# Sheet1.net
KiCad netlist of a schematic drawn in Altium Designer
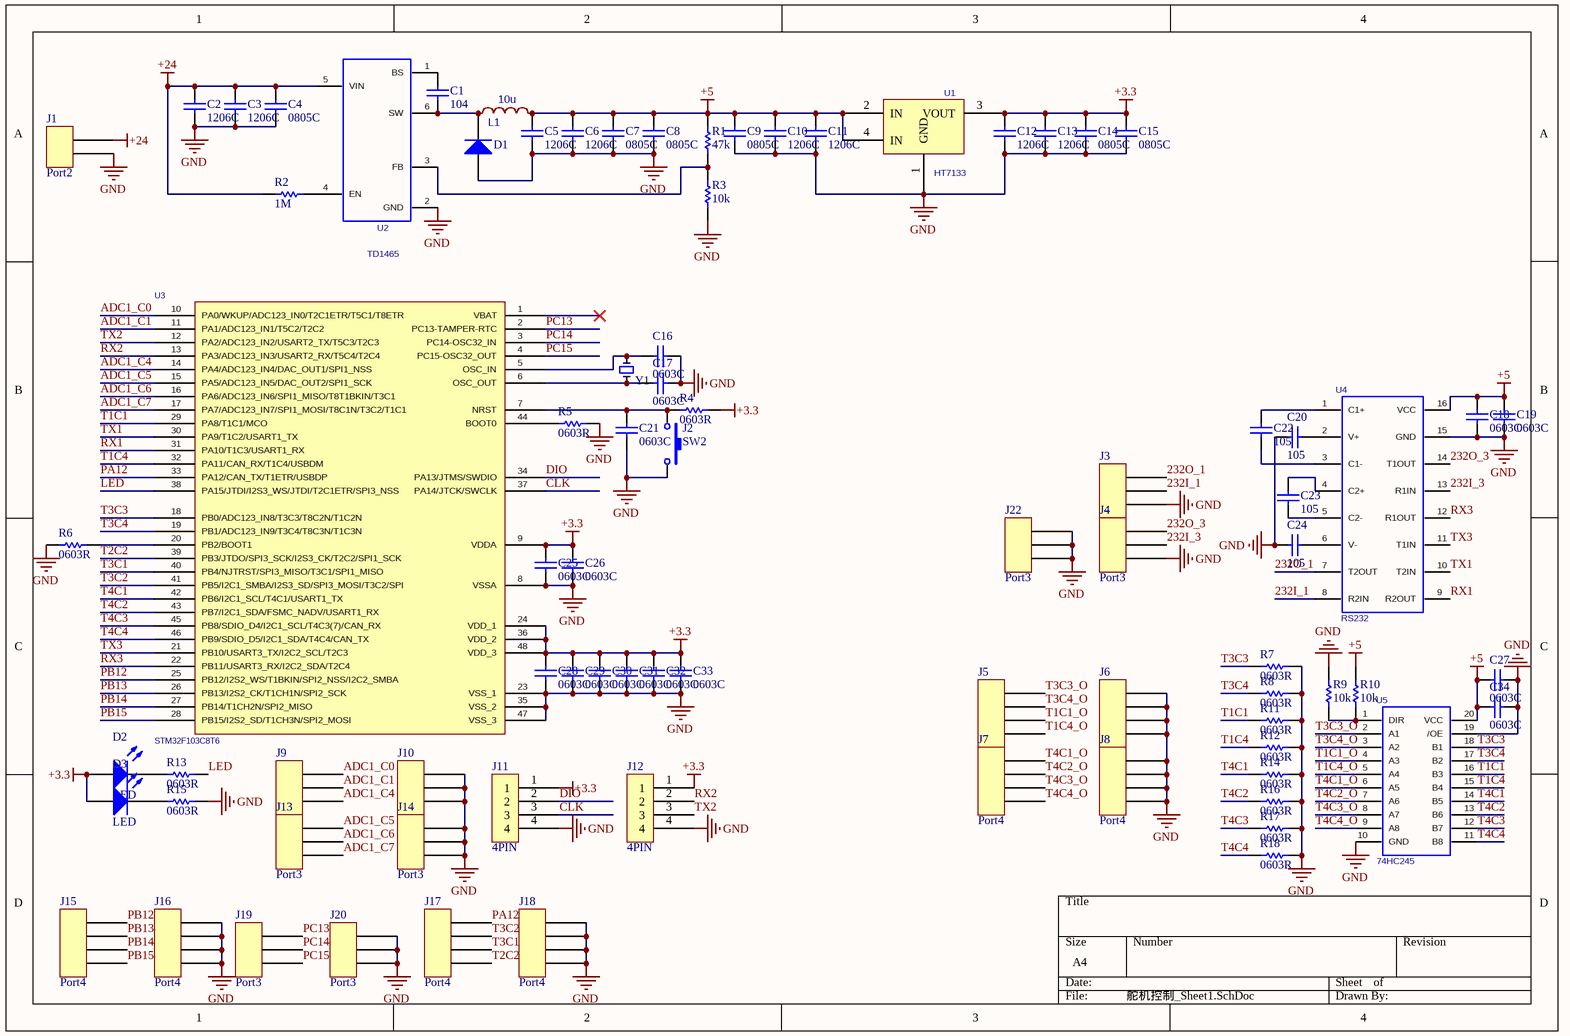
[diagram p0: 舵机控制_Sheet1.SchDoc]

(export (version "E")
  (design (tool "Eeschema 10.0.6"))
  (components
    (comp (ref "C1")
      (value "104")
      (footprint "0603C")
      (fields (field (name "PUBLISHER") "Altium Limited"))
      (libsource (lib "Schlib") (part "0603C"))
    )
    (comp (ref "C2") (value "1206C") (footprint "1206C") (libsource (lib "Schlib") (part "1206C")))
    (comp (ref "C3") (value "1206C") (footprint "1206C") (libsource (lib "Schlib") (part "1206C")))
    (comp (ref "C4") (value "0805C") (footprint "0805C") (libsource (lib "Schlib") (part "0805C")))
    (comp (ref "C5") (value "1206C") (footprint "1206C") (libsource (lib "Schlib") (part "1206C")))
    (comp (ref "C6") (value "1206C") (footprint "1206C") (libsource (lib "Schlib") (part "1206C")))
    (comp (ref "C7") (value "0805C") (footprint "0805C") (libsource (lib "Schlib") (part "0805C")))
    (comp (ref "C8") (value "0805C") (footprint "0805C") (libsource (lib "Schlib") (part "0805C")))
    (comp (ref "C9") (value "0805C") (footprint "0805C") (libsource (lib "Schlib") (part "0805C")))
    (comp (ref "C10") (value "1206C") (footprint "1206C") (libsource (lib "Schlib") (part "1206C")))
    (comp (ref "C11") (value "1206C") (footprint "1206C") (libsource (lib "Schlib") (part "1206C")))
    (comp (ref "C12") (value "1206C") (footprint "1206C") (libsource (lib "Schlib") (part "1206C")))
    (comp (ref "C13") (value "1206C") (footprint "1206C") (libsource (lib "Schlib") (part "1206C")))
    (comp (ref "C14") (value "0805C") (footprint "0805C") (libsource (lib "Schlib") (part "0805C")))
    (comp (ref "C15") (value "0805C") (footprint "0805C") (libsource (lib "Schlib") (part "0805C")))
    (comp (ref "C16")
      (value "0603C")
      (footprint "0603C")
      (fields (field (name "PUBLISHER") "Altium Limited"))
      (libsource (lib "Schlib") (part "0603C"))
    )
    (comp (ref "C17")
      (value "0603C")
      (footprint "0603C")
      (fields (field (name "PUBLISHER") "Altium Limited"))
      (libsource (lib "Schlib") (part "0603C"))
    )
    (comp (ref "C18")
      (value "0603C")
      (footprint "0603C")
      (fields (field (name "PUBLISHER") "Altium Limited"))
      (libsource (lib "Schlib") (part "0603C"))
    )
    (comp (ref "C19")
      (value "0603C")
      (footprint "0603C")
      (fields (field (name "PUBLISHER") "Altium Limited"))
      (libsource (lib "Schlib") (part "0603C"))
    )
    (comp (ref "C20")
      (value "105")
      (footprint "0603C")
      (fields (field (name "PUBLISHER") "Altium Limited"))
      (libsource (lib "Schlib") (part "0603C"))
    )
    (comp (ref "C21")
      (value "0603C")
      (footprint "0603C")
      (fields (field (name "PUBLISHER") "Altium Limited"))
      (libsource (lib "Schlib") (part "0603C"))
    )
    (comp (ref "C22")
      (value "105")
      (footprint "0603C")
      (fields (field (name "PUBLISHER") "Altium Limited"))
      (libsource (lib "Schlib") (part "0603C"))
    )
    (comp (ref "C23")
      (value "105")
      (footprint "0603C")
      (fields (field (name "PUBLISHER") "Altium Limited"))
      (libsource (lib "Schlib") (part "0603C"))
    )
    (comp (ref "C24")
      (value "105")
      (footprint "0603C")
      (fields (field (name "PUBLISHER") "Altium Limited"))
      (libsource (lib "Schlib") (part "0603C"))
    )
    (comp (ref "C25")
      (value "0603C")
      (footprint "0603C")
      (fields (field (name "PUBLISHER") "Altium Limited"))
      (libsource (lib "Schlib") (part "0603C"))
    )
    (comp (ref "C26")
      (value "0603C")
      (footprint "0603C")
      (fields (field (name "PUBLISHER") "Altium Limited"))
      (libsource (lib "Schlib") (part "0603C"))
    )
    (comp (ref "C27")
      (value "0603C")
      (footprint "0603C")
      (fields (field (name "PUBLISHER") "Altium Limited"))
      (libsource (lib "Schlib") (part "0603C"))
    )
    (comp (ref "C28")
      (value "0603C")
      (footprint "0603C")
      (fields (field (name "PUBLISHER") "Altium Limited"))
      (libsource (lib "Schlib") (part "0603C"))
    )
    (comp (ref "C29")
      (value "0603C")
      (footprint "0603C")
      (fields (field (name "PUBLISHER") "Altium Limited"))
      (libsource (lib "Schlib") (part "0603C"))
    )
    (comp (ref "C30")
      (value "0603C")
      (footprint "0603C")
      (fields (field (name "PUBLISHER") "Altium Limited"))
      (libsource (lib "Schlib") (part "0603C"))
    )
    (comp (ref "C31")
      (value "0603C")
      (footprint "0603C")
      (fields (field (name "PUBLISHER") "Altium Limited"))
      (libsource (lib "Schlib") (part "0603C"))
    )
    (comp (ref "C32")
      (value "0603C")
      (footprint "0603C")
      (fields (field (name "PUBLISHER") "Altium Limited"))
      (libsource (lib "Schlib") (part "0603C"))
    )
    (comp (ref "C33")
      (value "0603C")
      (footprint "0603C")
      (fields (field (name "PUBLISHER") "Altium Limited"))
      (libsource (lib "Schlib") (part "0603C"))
    )
    (comp (ref "C34")
      (value "0603C")
      (footprint "0603C")
      (fields (field (name "PUBLISHER") "Altium Limited"))
      (libsource (lib "Schlib") (part "0603C"))
    )
    (comp (ref "D1")
      (value "Diode 1N914")
      (footprint "SOD-123_L2.8-W1.8-LS3.7-RD")
      (fields (field (name "PUBLISHER") "Altium Limited"))
      (libsource (lib "Schlib") (part "Diode 1N914"))
    )
    (comp (ref "D2")
      (value "LED")
      (footprint "0603LED")
      (fields (field (name "PUBLISHER") "Altium Limited"))
      (libsource (lib "Schlib") (part "LED"))
    )
    (comp (ref "D3")
      (value "LED")
      (footprint "0603LED")
      (fields (field (name "PUBLISHER") "Altium Limited"))
      (libsource (lib "Schlib") (part "LED"))
    )
    (comp (ref "J1") (value "Port2") (footprint "Port2") (libsource (lib "Schlib") (part "Port2")))
    (comp (ref "J2")
      (value "SW2")
      (footprint "KEY-SMD_L6.2-W3.6-LS8.0")
      (fields (field (name "PUBLISHER") "Altium Limited"))
      (libsource (lib "Schlib") (part "SW2"))
    )
    (comp (ref "J3") (value "Port3") (footprint "Port3") (libsource (lib "Schlib") (part "Port3")))
    (comp (ref "J4") (value "Port3") (footprint "Port3") (libsource (lib "Schlib") (part "Port3")))
    (comp (ref "J5") (value "Port4") (footprint "Port4") (libsource (lib "Schlib") (part "Port4")))
    (comp (ref "J6") (value "Port4") (footprint "Port4") (libsource (lib "Schlib") (part "Port4")))
    (comp (ref "J7") (value "Port4") (footprint "Port4") (libsource (lib "Schlib") (part "Port4")))
    (comp (ref "J8") (value "Port4") (footprint "Port4") (libsource (lib "Schlib") (part "Port4")))
    (comp (ref "J9") (value "Port3") (footprint "Port3") (libsource (lib "Schlib") (part "Port3")))
    (comp (ref "J10") (value "Port3") (footprint "Port3") (libsource (lib "Schlib") (part "Port3")))
    (comp (ref "J11") (value "4PIN") (footprint "4PIN") (libsource (lib "Schlib") (part "4PIN")))
    (comp (ref "J12") (value "4PIN") (footprint "4PIN") (libsource (lib "Schlib") (part "4PIN")))
    (comp (ref "J13") (value "Port3") (footprint "Port3") (libsource (lib "Schlib") (part "Port3")))
    (comp (ref "J14") (value "Port3") (footprint "Port3") (libsource (lib "Schlib") (part "Port3")))
    (comp (ref "J15") (value "Port4") (footprint "Port4") (libsource (lib "Schlib") (part "Port4")))
    (comp (ref "J16") (value "Port4") (footprint "Port4") (libsource (lib "Schlib") (part "Port4")))
    (comp (ref "J17") (value "Port4") (footprint "Port4") (libsource (lib "Schlib") (part "Port4")))
    (comp (ref "J18") (value "Port4") (footprint "Port4") (libsource (lib "Schlib") (part "Port4")))
    (comp (ref "J19") (value "Port3") (footprint "Port3") (libsource (lib "Schlib") (part "Port3")))
    (comp (ref "J20") (value "Port3") (footprint "Port3") (libsource (lib "Schlib") (part "Port3")))
    (comp (ref "J22") (value "Port3") (footprint "Port3") (libsource (lib "Schlib") (part "Port3")))
    (comp (ref "L1")
      (value "10u")
      (footprint "L-SMD-0630")
      (fields
        (field (name "BOM_MANUFACTURER PART") "FXL0630-100-M")
        (field (name "BOM_SUPPLIER PART") "C167223")
        (field (name "CONTRIBUTOR") "LCSC")
      )
      (libsource (lib "Schlib") (part "L"))
    )
    (comp (ref "R1")
      (value "47k")
      (footprint "0603R")
      (fields (field (name "PUBLISHER") "Altium Limited"))
      (libsource (lib "Schlib") (part "0603R"))
    )
    (comp (ref "R2")
      (value "1M")
      (footprint "0603R")
      (fields (field (name "PUBLISHER") "Altium Limited"))
      (libsource (lib "Schlib") (part "0603R"))
    )
    (comp (ref "R3")
      (value "10k")
      (footprint "0603R")
      (fields (field (name "PUBLISHER") "Altium Limited"))
      (libsource (lib "Schlib") (part "0603R"))
    )
    (comp (ref "R4")
      (value "0603R")
      (footprint "0603R")
      (fields (field (name "PUBLISHER") "Altium Limited"))
      (libsource (lib "Schlib") (part "0603R"))
    )
    (comp (ref "R5")
      (value "0603R")
      (footprint "0603R")
      (fields (field (name "PUBLISHER") "Altium Limited"))
      (libsource (lib "Schlib") (part "0603R"))
    )
    (comp (ref "R6")
      (value "0603R")
      (footprint "0603R")
      (fields (field (name "PUBLISHER") "Altium Limited"))
      (libsource (lib "Schlib") (part "0603R"))
    )
    (comp (ref "R7")
      (value "0603R")
      (footprint "0603R")
      (fields (field (name "PUBLISHER") "Altium Limited"))
      (libsource (lib "Schlib") (part "0603R"))
    )
    (comp (ref "R8")
      (value "0603R")
      (footprint "0603R")
      (fields (field (name "PUBLISHER") "Altium Limited"))
      (libsource (lib "Schlib") (part "0603R"))
    )
    (comp (ref "R9")
      (value "10k")
      (footprint "0603R")
      (fields (field (name "PUBLISHER") "Altium Limited"))
      (libsource (lib "Schlib") (part "0603R"))
    )
    (comp (ref "R10")
      (value "10k")
      (footprint "0603R")
      (fields (field (name "PUBLISHER") "Altium Limited"))
      (libsource (lib "Schlib") (part "0603R"))
    )
    (comp (ref "R11")
      (value "0603R")
      (footprint "0603R")
      (fields (field (name "PUBLISHER") "Altium Limited"))
      (libsource (lib "Schlib") (part "0603R"))
    )
    (comp (ref "R12")
      (value "0603R")
      (footprint "0603R")
      (fields (field (name "PUBLISHER") "Altium Limited"))
      (libsource (lib "Schlib") (part "0603R"))
    )
    (comp (ref "R13")
      (value "0603R")
      (footprint "0603R")
      (fields (field (name "PUBLISHER") "Altium Limited"))
      (libsource (lib "Schlib") (part "0603R"))
    )
    (comp (ref "R14")
      (value "0603R")
      (footprint "0603R")
      (fields (field (name "PUBLISHER") "Altium Limited"))
      (libsource (lib "Schlib") (part "0603R"))
    )
    (comp (ref "R15")
      (value "0603R")
      (footprint "0603R")
      (fields (field (name "PUBLISHER") "Altium Limited"))
      (libsource (lib "Schlib") (part "0603R"))
    )
    (comp (ref "R16")
      (value "0603R")
      (footprint "0603R")
      (fields (field (name "PUBLISHER") "Altium Limited"))
      (libsource (lib "Schlib") (part "0603R"))
    )
    (comp (ref "R17")
      (value "0603R")
      (footprint "0603R")
      (fields (field (name "PUBLISHER") "Altium Limited"))
      (libsource (lib "Schlib") (part "0603R"))
    )
    (comp (ref "R18")
      (value "0603R")
      (footprint "0603R")
      (fields (field (name "PUBLISHER") "Altium Limited"))
      (libsource (lib "Schlib") (part "0603R"))
    )
    (comp (ref "U1")
      (value "HT7133")
      (footprint "SOT-89-3_L4.5-W2.5-P1.50-LS4.2-BR")
      (libsource (lib "Schlib") (part "HT7133"))
    )
    (comp (ref "U2") (value "TD1465") (footprint "SOT-23-6") (libsource (lib "Schlib") (part "TD1465")))
    (comp (ref "U3")
      (value "STM32F103C8T6")
      (footprint "LQFP-48_L7.0-W7.0-P0.50-LS9.0-BL")
      (libsource (lib "Schlib") (part "STM32F103C8T6"))
    )
    (comp (ref "U4")
      (value "RS232")
      (footprint "SOP-16_L9.9-W3.9-P1.27-LS6.1-BL")
      (libsource (lib "Schlib") (part "RS232"))
    )
    (comp (ref "U5")
      (value "74HC245")
      (footprint "TSSOP-20_L6.5-W4.4-P0.65-LS6.4-BL")
      (libsource (lib "Schlib") (part "74HC245"))
    )
    (comp (ref "Y1") (value "XTAL") (footprint "XTAL") (libsource (lib "Schlib") (part "XTAL")))
  )
  (nets
    (net (code "1") (name "+3.3") (class "Default")
      (node (ref "C12") (pin "2") (pinfunction "2_2") (pintype "passive"))
      (node (ref "C13") (pin "2") (pinfunction "2_2") (pintype "passive"))
      (node (ref "C14") (pin "2") (pinfunction "2_2") (pintype "passive"))
      (node (ref "C15") (pin "2") (pinfunction "2_2") (pintype "passive"))
      (node (ref "C25") (pin "2") (pinfunction "2_2") (pintype "passive"))
      (node (ref "C26") (pin "2") (pinfunction "2_2") (pintype "passive"))
      (node (ref "C28") (pin "2") (pinfunction "2_2") (pintype "passive"))
      (node (ref "C29") (pin "2") (pinfunction "2_2") (pintype "passive"))
      (node (ref "C30") (pin "2") (pinfunction "2_2") (pintype "passive"))
      (node (ref "C31") (pin "2") (pinfunction "2_2") (pintype "passive"))
      (node (ref "C32") (pin "2") (pinfunction "2_2") (pintype "passive"))
      (node (ref "C33") (pin "2") (pinfunction "2_2") (pintype "passive"))
      (node (ref "D2") (pin "1") (pinfunction "A_1") (pintype "passive"))
      (node (ref "D3") (pin "1") (pinfunction "A_1") (pintype "passive"))
      (node (ref "J11") (pin "1") (pinfunction "1_1") (pintype "passive"))
      (node (ref "J12") (pin "1") (pinfunction "1_1") (pintype "passive"))
      (node (ref "R4") (pin "1") (pinfunction "1_1") (pintype "passive"))
      (node (ref "U1") (pin "3") (pinfunction "VOUT_3") (pintype "passive"))
      (node (ref "U3") (pin "24") (pinfunction "VDD_1_24") (pintype "passive"))
      (node (ref "U3") (pin "36") (pinfunction "VDD_2_36") (pintype "passive"))
      (node (ref "U3") (pin "48") (pinfunction "VDD_3_48") (pintype "passive"))
      (node (ref "U3") (pin "9") (pinfunction "VDDA_9") (pintype "passive"))
    )
    (net (code "2") (name "+5") (class "Default")
      (node (ref "C10") (pin "2") (pinfunction "2_2") (pintype "passive"))
      (node (ref "C11") (pin "2") (pinfunction "2_2") (pintype "passive"))
      (node (ref "C18") (pin "2") (pinfunction "2_2") (pintype "passive"))
      (node (ref "C19") (pin "2") (pinfunction "2_2") (pintype "passive"))
      (node (ref "C27") (pin "2") (pinfunction "2_2") (pintype "passive"))
      (node (ref "C34") (pin "2") (pinfunction "2_2") (pintype "passive"))
      (node (ref "C5") (pin "2") (pinfunction "2_2") (pintype "passive"))
      (node (ref "C6") (pin "2") (pinfunction "2_2") (pintype "passive"))
      (node (ref "C7") (pin "2") (pinfunction "2_2") (pintype "passive"))
      (node (ref "C8") (pin "2") (pinfunction "2_2") (pintype "passive"))
      (node (ref "C9") (pin "2") (pinfunction "2_2") (pintype "passive"))
      (node (ref "L1") (pin "2") (pinfunction "2_2") (pintype "passive"))
      (node (ref "R1") (pin "2") (pinfunction "2_2") (pintype "passive"))
      (node (ref "R10") (pin "2") (pinfunction "2_2") (pintype "passive"))
      (node (ref "U1") (pin "2") (pinfunction "IN_2") (pintype "passive"))
      (node (ref "U1") (pin "4") (pinfunction "IN_4") (pintype "passive"))
      (node (ref "U4") (pin "16") (pinfunction "VCC_16") (pintype "passive"))
      (node (ref "U5") (pin "20") (pinfunction "VCC_20") (pintype "passive"))
    )
    (net (code "3") (name "+24") (class "Default")
      (node (ref "C2") (pin "2") (pinfunction "2_2") (pintype "passive"))
      (node (ref "C3") (pin "2") (pinfunction "2_2") (pintype "passive"))
      (node (ref "C4") (pin "2") (pinfunction "2_2") (pintype "passive"))
      (node (ref "J1") (pin "2") (pinfunction "2_2") (pintype "passive"))
      (node (ref "R2") (pin "1") (pinfunction "1_1") (pintype "passive"))
      (node (ref "U2") (pin "5") (pinfunction "VIN_5") (pintype "passive"))
    )
    (net (code "4") (name "/232I_1") (class "Default")
      (node (ref "J3") (pin "2") (pinfunction "2_2") (pintype "passive"))
      (node (ref "U4") (pin "8") (pinfunction "R2IN_8") (pintype "passive"))
    )
    (net (code "5") (name "/232I_3") (class "Default")
      (node (ref "J4") (pin "2") (pinfunction "2_2") (pintype "passive"))
      (node (ref "U4") (pin "13") (pinfunction "R1IN_13") (pintype "passive"))
    )
    (net (code "6") (name "/232O_1") (class "Default")
      (node (ref "J3") (pin "1") (pinfunction "1_1") (pintype "passive"))
      (node (ref "U4") (pin "7") (pinfunction "T2OUT_7") (pintype "passive"))
    )
    (net (code "7") (name "/232O_3") (class "Default")
      (node (ref "J4") (pin "1") (pinfunction "1_1") (pintype "passive"))
      (node (ref "U4") (pin "14") (pinfunction "T1OUT_14") (pintype "passive"))
    )
    (net (code "8") (name "/ADC1_C0") (class "Default")
      (node (ref "J9") (pin "1") (pinfunction "1_1") (pintype "passive"))
      (node (ref "U3") (pin "10") (pinfunction "PA0/WKUP/ADC123_IN0/T2C1ETR/T5C1/T8ETR_10") (pintype "passive"))
    )
    (net (code "9") (name "/ADC1_C1") (class "Default")
      (node (ref "J9") (pin "2") (pinfunction "2_2") (pintype "passive"))
      (node (ref "U3") (pin "11") (pinfunction "PA1/ADC123_IN1/T5C2/T2C2_11") (pintype "passive"))
    )
    (net (code "10") (name "/ADC1_C4") (class "Default")
      (node (ref "J9") (pin "3") (pinfunction "3_3") (pintype "passive"))
      (node (ref "U3") (pin "14") (pinfunction "PA4/ADC123_IN4/DAC_OUT1/SPI1_NSS_14") (pintype "passive"))
    )
    (net (code "11") (name "/ADC1_C5") (class "Default")
      (node (ref "J13") (pin "1") (pinfunction "1_1") (pintype "passive"))
      (node (ref "U3") (pin "15") (pinfunction "PA5/ADC123_IN5/DAC_OUT2/SPI1_SCK_15") (pintype "passive"))
    )
    (net (code "12") (name "/ADC1_C6") (class "Default")
      (node (ref "J13") (pin "2") (pinfunction "2_2") (pintype "passive"))
      (node (ref "U3") (pin "16") (pinfunction "PA6/ADC123_IN6/SPI1_MISO/T8T1BKIN/T3C1_16") (pintype "passive"))
    )
    (net (code "13") (name "/ADC1_C7") (class "Default")
      (node (ref "J13") (pin "3") (pinfunction "3_3") (pintype "passive"))
      (node (ref "U3") (pin "17") (pinfunction "PA7/ADC123_IN7/SPI1_MOSI/T8C1N/T3C2/T1C1_17") (pintype "passive"))
    )
    (net (code "14") (name "/CLK") (class "Default")
      (node (ref "J11") (pin "3") (pinfunction "3_3") (pintype "passive"))
      (node (ref "U3") (pin "37") (pinfunction "PA14/JTCK/SWCLK_37") (pintype "passive"))
    )
    (net (code "15") (name "/DIO") (class "Default")
      (node (ref "J11") (pin "2") (pinfunction "2_2") (pintype "passive"))
      (node (ref "U3") (pin "34") (pinfunction "PA13/JTMS/SWDIO_34") (pintype "passive"))
    )
    (net (code "16") (name "/LED") (class "Default")
      (node (ref "R13") (pin "2") (pinfunction "2_2") (pintype "passive"))
      (node (ref "U3") (pin "38") (pinfunction "PA15/JTDI/I2S3_WS/JTDI/T2C1ETR/SPI3_NSS_38") (pintype "passive"))
    )
    (net (code "17") (name "/PA12") (class "Default")
      (node (ref "J17") (pin "1") (pinfunction "1_1") (pintype "passive"))
      (node (ref "U3") (pin "33") (pinfunction "PA12/CAN_TX/T1ETR/USBDP_33") (pintype "passive"))
    )
    (net (code "18") (name "/PB12") (class "Default")
      (node (ref "J15") (pin "1") (pinfunction "1_1") (pintype "passive"))
      (node (ref "U3") (pin "25") (pinfunction "PB12/I2S2_WS/T1BKIN/SPI2_NSS/I2C2_SMBA_25") (pintype "passive"))
    )
    (net (code "19") (name "/PB13") (class "Default")
      (node (ref "J15") (pin "2") (pinfunction "2_2") (pintype "passive"))
      (node (ref "U3") (pin "26") (pinfunction "PB13/I2S2_CK/T1CH1N/SPI2_SCK_26") (pintype "passive"))
    )
    (net (code "20") (name "/PB14") (class "Default")
      (node (ref "J15") (pin "3") (pinfunction "3_3") (pintype "passive"))
      (node (ref "U3") (pin "27") (pinfunction "PB14/T1CH2N/SPI2_MISO_27") (pintype "passive"))
    )
    (net (code "21") (name "/PB15") (class "Default")
      (node (ref "J15") (pin "4") (pinfunction "4_4") (pintype "passive"))
      (node (ref "U3") (pin "28") (pinfunction "PB15/I2S2_SD/T1CH3N/SPI2_MOSI_28") (pintype "passive"))
    )
    (net (code "22") (name "/PC13") (class "Default")
      (node (ref "J19") (pin "1") (pinfunction "1_1") (pintype "passive"))
      (node (ref "U3") (pin "2") (pinfunction "PC13-TAMPER-RTC_2") (pintype "passive"))
    )
    (net (code "23") (name "/PC14") (class "Default")
      (node (ref "J19") (pin "2") (pinfunction "2_2") (pintype "passive"))
      (node (ref "U3") (pin "3") (pinfunction "PC14-OSC32_IN_3") (pintype "passive"))
    )
    (net (code "24") (name "/PC15") (class "Default")
      (node (ref "J19") (pin "3") (pinfunction "3_3") (pintype "passive"))
      (node (ref "U3") (pin "4") (pinfunction "PC15-OSC32_OUT_4") (pintype "passive"))
    )
    (net (code "25") (name "/RX1") (class "Default")
      (node (ref "U3") (pin "31") (pinfunction "PA10/T1C3/USART1_RX_31") (pintype "passive"))
      (node (ref "U4") (pin "9") (pinfunction "R2OUT_9") (pintype "passive"))
    )
    (net (code "26") (name "/RX2") (class "Default")
      (node (ref "J12") (pin "2") (pinfunction "2_2") (pintype "passive"))
      (node (ref "U3") (pin "13") (pinfunction "PA3/ADC123_IN3/USART2_RX/T5C4/T2C4_13") (pintype "passive"))
    )
    (net (code "27") (name "/RX3") (class "Default")
      (node (ref "U3") (pin "22") (pinfunction "PB11/USART3_RX/I2C2_SDA/T2C4_22") (pintype "passive"))
      (node (ref "U4") (pin "12") (pinfunction "R1OUT_12") (pintype "passive"))
    )
    (net (code "28") (name "/T1C1") (class "Default")
      (node (ref "R11") (pin "1") (pinfunction "1_1") (pintype "passive"))
      (node (ref "U3") (pin "29") (pinfunction "PA8/T1C1/MCO_29") (pintype "passive"))
      (node (ref "U5") (pin "16") (pinfunction "B3_16") (pintype "passive"))
    )
    (net (code "29") (name "/T1C1_O") (class "Default")
      (node (ref "J5") (pin "3") (pinfunction "3_3") (pintype "passive"))
      (node (ref "U5") (pin "4") (pinfunction "A3_4") (pintype "passive"))
    )
    (net (code "30") (name "/T1C4") (class "Default")
      (node (ref "R12") (pin "1") (pinfunction "1_1") (pintype "passive"))
      (node (ref "U3") (pin "32") (pinfunction "PA11/CAN_RX/T1C4/USBDM_32") (pintype "passive"))
      (node (ref "U5") (pin "15") (pinfunction "B4_15") (pintype "passive"))
    )
    (net (code "31") (name "/T1C4_O") (class "Default")
      (node (ref "J5") (pin "4") (pinfunction "4_4") (pintype "passive"))
      (node (ref "U5") (pin "5") (pinfunction "A4_5") (pintype "passive"))
    )
    (net (code "32") (name "/T2C2") (class "Default")
      (node (ref "J17") (pin "4") (pinfunction "4_4") (pintype "passive"))
      (node (ref "U3") (pin "39") (pinfunction "PB3/JTDO/SPI3_SCK/I2S3_CK/T2C2/SPI1_SCK_39") (pintype "passive"))
    )
    (net (code "33") (name "/T3C1") (class "Default")
      (node (ref "J17") (pin "3") (pinfunction "3_3") (pintype "passive"))
      (node (ref "U3") (pin "40") (pinfunction "PB4/NJTRST/SPI3_MISO/T3C1/SPI1_MISO_40") (pintype "passive"))
    )
    (net (code "34") (name "/T3C2") (class "Default")
      (node (ref "J17") (pin "2") (pinfunction "2_2") (pintype "passive"))
      (node (ref "U3") (pin "41") (pinfunction "PB5/I2C1_SMBA/I2S3_SD/SPI3_MOSI/T3C2/SPI_41") (pintype "passive"))
    )
    (net (code "35") (name "/T3C3") (class "Default")
      (node (ref "R7") (pin "1") (pinfunction "1_1") (pintype "passive"))
      (node (ref "U3") (pin "18") (pinfunction "PB0/ADC123_IN8/T3C3/T8C2N/T1C2N_18") (pintype "passive"))
      (node (ref "U5") (pin "18") (pinfunction "B1_18") (pintype "passive"))
    )
    (net (code "36") (name "/T3C3_O") (class "Default")
      (node (ref "J5") (pin "1") (pinfunction "1_1") (pintype "passive"))
      (node (ref "U5") (pin "2") (pinfunction "A1_2") (pintype "passive"))
    )
    (net (code "37") (name "/T3C4") (class "Default")
      (node (ref "R8") (pin "1") (pinfunction "1_1") (pintype "passive"))
      (node (ref "U3") (pin "19") (pinfunction "PB1/ADC123_IN9/T3C4/T8C3N/T1C3N_19") (pintype "passive"))
      (node (ref "U5") (pin "17") (pinfunction "B2_17") (pintype "passive"))
    )
    (net (code "38") (name "/T3C4_O") (class "Default")
      (node (ref "J5") (pin "2") (pinfunction "2_2") (pintype "passive"))
      (node (ref "U5") (pin "3") (pinfunction "A2_3") (pintype "passive"))
    )
    (net (code "39") (name "/T4C1") (class "Default")
      (node (ref "R14") (pin "1") (pinfunction "1_1") (pintype "passive"))
      (node (ref "U3") (pin "42") (pinfunction "PB6/I2C1_SCL/T4C1/USART1_TX_42") (pintype "passive"))
      (node (ref "U5") (pin "14") (pinfunction "B5_14") (pintype "passive"))
    )
    (net (code "40") (name "/T4C1_O") (class "Default")
      (node (ref "J7") (pin "1") (pinfunction "1_1") (pintype "passive"))
      (node (ref "U5") (pin "6") (pinfunction "A5_6") (pintype "passive"))
    )
    (net (code "41") (name "/T4C2") (class "Default")
      (node (ref "R16") (pin "1") (pinfunction "1_1") (pintype "passive"))
      (node (ref "U3") (pin "43") (pinfunction "PB7/I2C1_SDA/FSMC_NADV/USART1_RX_43") (pintype "passive"))
      (node (ref "U5") (pin "13") (pinfunction "B6_13") (pintype "passive"))
    )
    (net (code "42") (name "/T4C2_O") (class "Default")
      (node (ref "J7") (pin "2") (pinfunction "2_2") (pintype "passive"))
      (node (ref "U5") (pin "7") (pinfunction "A6_7") (pintype "passive"))
    )
    (net (code "43") (name "/T4C3") (class "Default")
      (node (ref "R17") (pin "1") (pinfunction "1_1") (pintype "passive"))
      (node (ref "U3") (pin "45") (pinfunction "PB8/SDIO_D4/I2C1_SCL/T4C3(7)/CAN_RX_45") (pintype "passive"))
      (node (ref "U5") (pin "12") (pinfunction "B7_12") (pintype "passive"))
    )
    (net (code "44") (name "/T4C3_O") (class "Default")
      (node (ref "J7") (pin "3") (pinfunction "3_3") (pintype "passive"))
      (node (ref "U5") (pin "8") (pinfunction "A7_8") (pintype "passive"))
    )
    (net (code "45") (name "/T4C4") (class "Default")
      (node (ref "R18") (pin "1") (pinfunction "1_1") (pintype "passive"))
      (node (ref "U3") (pin "46") (pinfunction "PB9/SDIO_D5/I2C1_SDA/T4C4/CAN_TX_46") (pintype "passive"))
      (node (ref "U5") (pin "11") (pinfunction "B8_11") (pintype "passive"))
    )
    (net (code "46") (name "/T4C4_O") (class "Default")
      (node (ref "J7") (pin "4") (pinfunction "4_4") (pintype "passive"))
      (node (ref "U5") (pin "9") (pinfunction "A8_9") (pintype "passive"))
    )
    (net (code "47") (name "/TX1") (class "Default")
      (node (ref "U3") (pin "30") (pinfunction "PA9/T1C2/USART1_TX_30") (pintype "passive"))
      (node (ref "U4") (pin "10") (pinfunction "T2IN_10") (pintype "passive"))
    )
    (net (code "48") (name "/TX2") (class "Default")
      (node (ref "J12") (pin "3") (pinfunction "3_3") (pintype "passive"))
      (node (ref "U3") (pin "12") (pinfunction "PA2/ADC123_IN2/USART2_TX/T5C3/T2C3_12") (pintype "passive"))
    )
    (net (code "49") (name "/TX3") (class "Default")
      (node (ref "U3") (pin "21") (pinfunction "PB10/USART3_TX/I2C2_SCL/T2C3_21") (pintype "passive"))
      (node (ref "U4") (pin "11") (pinfunction "T1IN_11") (pintype "passive"))
    )
    (net (code "50") (name "GND") (class "Default")
      (node (ref "C10") (pin "1") (pinfunction "1_1") (pintype "passive"))
      (node (ref "C11") (pin "1") (pinfunction "1_1") (pintype "passive"))
      (node (ref "C12") (pin "1") (pinfunction "1_1") (pintype "passive"))
      (node (ref "C13") (pin "1") (pinfunction "1_1") (pintype "passive"))
      (node (ref "C14") (pin "1") (pinfunction "1_1") (pintype "passive"))
      (node (ref "C15") (pin "1") (pinfunction "1_1") (pintype "passive"))
      (node (ref "C16") (pin "2") (pinfunction "2_2") (pintype "passive"))
      (node (ref "C17") (pin "2") (pinfunction "2_2") (pintype "passive"))
      (node (ref "C18") (pin "1") (pinfunction "1_1") (pintype "passive"))
      (node (ref "C19") (pin "1") (pinfunction "1_1") (pintype "passive"))
      (node (ref "C2") (pin "1") (pinfunction "1_1") (pintype "passive"))
      (node (ref "C20") (pin "2") (pinfunction "2_2") (pintype "passive"))
      (node (ref "C21") (pin "1") (pinfunction "1_1") (pintype "passive"))
      (node (ref "C24") (pin "2") (pinfunction "2_2") (pintype "passive"))
      (node (ref "C25") (pin "1") (pinfunction "1_1") (pintype "passive"))
      (node (ref "C26") (pin "1") (pinfunction "1_1") (pintype "passive"))
      (node (ref "C27") (pin "1") (pinfunction "1_1") (pintype "passive"))
      (node (ref "C28") (pin "1") (pinfunction "1_1") (pintype "passive"))
      (node (ref "C29") (pin "1") (pinfunction "1_1") (pintype "passive"))
      (node (ref "C3") (pin "1") (pinfunction "1_1") (pintype "passive"))
      (node (ref "C30") (pin "1") (pinfunction "1_1") (pintype "passive"))
      (node (ref "C31") (pin "1") (pinfunction "1_1") (pintype "passive"))
      (node (ref "C32") (pin "1") (pinfunction "1_1") (pintype "passive"))
      (node (ref "C33") (pin "1") (pinfunction "1_1") (pintype "passive"))
      (node (ref "C34") (pin "1") (pinfunction "1_1") (pintype "passive"))
      (node (ref "C4") (pin "1") (pinfunction "1_1") (pintype "passive"))
      (node (ref "C5") (pin "1") (pinfunction "1_1") (pintype "passive"))
      (node (ref "C6") (pin "1") (pinfunction "1_1") (pintype "passive"))
      (node (ref "C7") (pin "1") (pinfunction "1_1") (pintype "passive"))
      (node (ref "C8") (pin "1") (pinfunction "1_1") (pintype "passive"))
      (node (ref "C9") (pin "1") (pinfunction "1_1") (pintype "passive"))
      (node (ref "D1") (pin "1") (pinfunction "A_1") (pintype "passive"))
      (node (ref "J1") (pin "1") (pinfunction "1_1") (pintype "passive"))
      (node (ref "J10") (pin "1") (pinfunction "1_1") (pintype "passive"))
      (node (ref "J10") (pin "2") (pinfunction "2_2") (pintype "passive"))
      (node (ref "J10") (pin "3") (pinfunction "3_3") (pintype "passive"))
      (node (ref "J11") (pin "4") (pinfunction "4_4") (pintype "passive"))
      (node (ref "J12") (pin "4") (pinfunction "4_4") (pintype "passive"))
      (node (ref "J14") (pin "1") (pinfunction "1_1") (pintype "passive"))
      (node (ref "J14") (pin "2") (pinfunction "2_2") (pintype "passive"))
      (node (ref "J14") (pin "3") (pinfunction "3_3") (pintype "passive"))
      (node (ref "J16") (pin "1") (pinfunction "1_1") (pintype "passive"))
      (node (ref "J16") (pin "2") (pinfunction "2_2") (pintype "passive"))
      (node (ref "J16") (pin "3") (pinfunction "3_3") (pintype "passive"))
      (node (ref "J16") (pin "4") (pinfunction "4_4") (pintype "passive"))
      (node (ref "J18") (pin "1") (pinfunction "1_1") (pintype "passive"))
      (node (ref "J18") (pin "2") (pinfunction "2_2") (pintype "passive"))
      (node (ref "J18") (pin "3") (pinfunction "3_3") (pintype "passive"))
      (node (ref "J18") (pin "4") (pinfunction "4_4") (pintype "passive"))
      (node (ref "J2") (pin "2") (pinfunction "2_2") (pintype "passive"))
      (node (ref "J20") (pin "1") (pinfunction "1_1") (pintype "passive"))
      (node (ref "J20") (pin "2") (pinfunction "2_2") (pintype "passive"))
      (node (ref "J20") (pin "3") (pinfunction "3_3") (pintype "passive"))
      (node (ref "J22") (pin "1") (pinfunction "1_1") (pintype "passive"))
      (node (ref "J22") (pin "2") (pinfunction "2_2") (pintype "passive"))
      (node (ref "J22") (pin "3") (pinfunction "3_3") (pintype "passive"))
      (node (ref "J3") (pin "3") (pinfunction "3_3") (pintype "passive"))
      (node (ref "J4") (pin "3") (pinfunction "3_3") (pintype "passive"))
      (node (ref "J6") (pin "1") (pinfunction "1_1") (pintype "passive"))
      (node (ref "J6") (pin "2") (pinfunction "2_2") (pintype "passive"))
      (node (ref "J6") (pin "3") (pinfunction "3_3") (pintype "passive"))
      (node (ref "J6") (pin "4") (pinfunction "4_4") (pintype "passive"))
      (node (ref "J8") (pin "1") (pinfunction "1_1") (pintype "passive"))
      (node (ref "J8") (pin "2") (pinfunction "2_2") (pintype "passive"))
      (node (ref "J8") (pin "3") (pinfunction "3_3") (pintype "passive"))
      (node (ref "J8") (pin "4") (pinfunction "4_4") (pintype "passive"))
      (node (ref "R11") (pin "2") (pinfunction "2_2") (pintype "passive"))
      (node (ref "R12") (pin "2") (pinfunction "2_2") (pintype "passive"))
      (node (ref "R14") (pin "2") (pinfunction "2_2") (pintype "passive"))
      (node (ref "R15") (pin "2") (pinfunction "2_2") (pintype "passive"))
      (node (ref "R16") (pin "2") (pinfunction "2_2") (pintype "passive"))
      (node (ref "R17") (pin "2") (pinfunction "2_2") (pintype "passive"))
      (node (ref "R18") (pin "2") (pinfunction "2_2") (pintype "passive"))
      (node (ref "R3") (pin "1") (pinfunction "1_1") (pintype "passive"))
      (node (ref "R5") (pin "1") (pinfunction "1_1") (pintype "passive"))
      (node (ref "R6") (pin "1") (pinfunction "1_1") (pintype "passive"))
      (node (ref "R7") (pin "2") (pinfunction "2_2") (pintype "passive"))
      (node (ref "R8") (pin "2") (pinfunction "2_2") (pintype "passive"))
      (node (ref "R9") (pin "2") (pinfunction "2_2") (pintype "passive"))
      (node (ref "U1") (pin "1") (pinfunction "GND_1") (pintype "passive"))
      (node (ref "U2") (pin "2") (pinfunction "GND_2") (pintype "passive"))
      (node (ref "U3") (pin "23") (pinfunction "VSS_1_23") (pintype "passive"))
      (node (ref "U3") (pin "35") (pinfunction "VSS_2_35") (pintype "passive"))
      (node (ref "U3") (pin "47") (pinfunction "VSS_3_47") (pintype "passive"))
      (node (ref "U3") (pin "8") (pinfunction "VSSA_8") (pintype "passive"))
      (node (ref "U4") (pin "15") (pinfunction "GND_15") (pintype "passive"))
      (node (ref "U5") (pin "10") (pinfunction "GND_10") (pintype "passive"))
      (node (ref "U5") (pin "19") (pinfunction "/OE_19") (pintype "passive"))
    )
    (net (code "51") (name "Net-(D1-K)") (class "Default")
      (node (ref "C1") (pin "1") (pinfunction "1_1") (pintype "passive"))
      (node (ref "D1") (pin "2") (pinfunction "K_2") (pintype "passive"))
      (node (ref "L1") (pin "1") (pinfunction "1_1") (pintype "passive"))
      (node (ref "U2") (pin "6") (pinfunction "SW_6") (pintype "passive"))
    )
    (net (code "52") (name "Net-(D2-K)") (class "Default")
      (node (ref "D2") (pin "2") (pinfunction "K_2") (pintype "passive"))
      (node (ref "R13") (pin "1") (pinfunction "1_1") (pintype "passive"))
    )
    (net (code "53") (name "Net-(D3-K)") (class "Default")
      (node (ref "D3") (pin "2") (pinfunction "K_2") (pintype "passive"))
      (node (ref "R15") (pin "1") (pinfunction "1_1") (pintype "passive"))
    )
    (net (code "54") (name "Net-(U2-BS)") (class "Default")
      (node (ref "C1") (pin "2") (pinfunction "2_2") (pintype "passive"))
      (node (ref "U2") (pin "1") (pinfunction "BS_1") (pintype "passive"))
    )
    (net (code "55") (name "Net-(U2-EN)") (class "Default")
      (node (ref "R2") (pin "2") (pinfunction "2_2") (pintype "passive"))
      (node (ref "U2") (pin "4") (pinfunction "EN_4") (pintype "passive"))
    )
    (net (code "56") (name "Net-(U2-FB)") (class "Default")
      (node (ref "R1") (pin "1") (pinfunction "1_1") (pintype "passive"))
      (node (ref "R3") (pin "2") (pinfunction "2_2") (pintype "passive"))
      (node (ref "U2") (pin "3") (pinfunction "FB_3") (pintype "passive"))
    )
    (net (code "57") (name "Net-(U3-BOOT0)") (class "Default")
      (node (ref "R5") (pin "2") (pinfunction "2_2") (pintype "passive"))
      (node (ref "U3") (pin "44") (pinfunction "BOOT0_44") (pintype "passive"))
    )
    (net (code "58") (name "Net-(U3-NRST)") (class "Default")
      (node (ref "C21") (pin "2") (pinfunction "2_2") (pintype "passive"))
      (node (ref "J2") (pin "1") (pinfunction "1_1") (pintype "passive"))
      (node (ref "R4") (pin "2") (pinfunction "2_2") (pintype "passive"))
      (node (ref "U3") (pin "7") (pinfunction "NRST_7") (pintype "passive"))
    )
    (net (code "59") (name "Net-(U3-OSC_IN)") (class "Default")
      (node (ref "C16") (pin "1") (pinfunction "1_1") (pintype "passive"))
      (node (ref "U3") (pin "5") (pinfunction "OSC_IN_5") (pintype "passive"))
      (node (ref "Y1") (pin "2") (pinfunction "2_2") (pintype "passive"))
    )
    (net (code "60") (name "Net-(U3-OSC_OUT)") (class "Default")
      (node (ref "C17") (pin "1") (pinfunction "1_1") (pintype "passive"))
      (node (ref "U3") (pin "6") (pinfunction "OSC_OUT_6") (pintype "passive"))
      (node (ref "Y1") (pin "1") (pinfunction "1_1") (pintype "passive"))
    )
    (net (code "61") (name "Net-(U3-PB2{slash}BOOT1)") (class "Default")
      (node (ref "R6") (pin "2") (pinfunction "2_2") (pintype "passive"))
      (node (ref "U3") (pin "20") (pinfunction "PB2/BOOT1_20") (pintype "passive"))
    )
    (net (code "62") (name "Net-(U4-C1+)") (class "Default")
      (node (ref "C22") (pin "2") (pinfunction "2_2") (pintype "passive"))
      (node (ref "U4") (pin "1") (pinfunction "C1+_1") (pintype "passive"))
    )
    (net (code "63") (name "Net-(U4-C1-)") (class "Default")
      (node (ref "C22") (pin "1") (pinfunction "1_1") (pintype "passive"))
      (node (ref "U4") (pin "3") (pinfunction "C1-_3") (pintype "passive"))
    )
    (net (code "64") (name "Net-(U4-C2+)") (class "Default")
      (node (ref "C23") (pin "2") (pinfunction "2_2") (pintype "passive"))
      (node (ref "U4") (pin "4") (pinfunction "C2+_4") (pintype "passive"))
    )
    (net (code "65") (name "Net-(U4-C2-)") (class "Default")
      (node (ref "C23") (pin "1") (pinfunction "1_1") (pintype "passive"))
      (node (ref "U4") (pin "5") (pinfunction "C2-_5") (pintype "passive"))
    )
    (net (code "66") (name "Net-(U4-V+)") (class "Default")
      (node (ref "C20") (pin "1") (pinfunction "1_1") (pintype "passive"))
      (node (ref "U4") (pin "2") (pinfunction "V+_2") (pintype "passive"))
    )
    (net (code "67") (name "Net-(U4-V-)") (class "Default")
      (node (ref "C24") (pin "1") (pinfunction "1_1") (pintype "passive"))
      (node (ref "U4") (pin "6") (pinfunction "V-_6") (pintype "passive"))
    )
    (net (code "68") (name "Net-(U5-DIR)") (class "Default")
      (node (ref "R10") (pin "1") (pinfunction "1_1") (pintype "passive"))
      (node (ref "R9") (pin "1") (pinfunction "1_1") (pintype "passive"))
      (node (ref "U5") (pin "1") (pinfunction "DIR_1") (pintype "passive"))
    )
    (net (code "69") (name "unconnected-(U3-VBAT-Pad1)") (class "Default")
      (node (ref "U3") (pin "1") (pinfunction "VBAT_1") (pintype "passive+no_connect"))
    )
  )
)
